# Throwing_POW_Supply.net
KiCad netlist of a schematic drawn in EAGLE
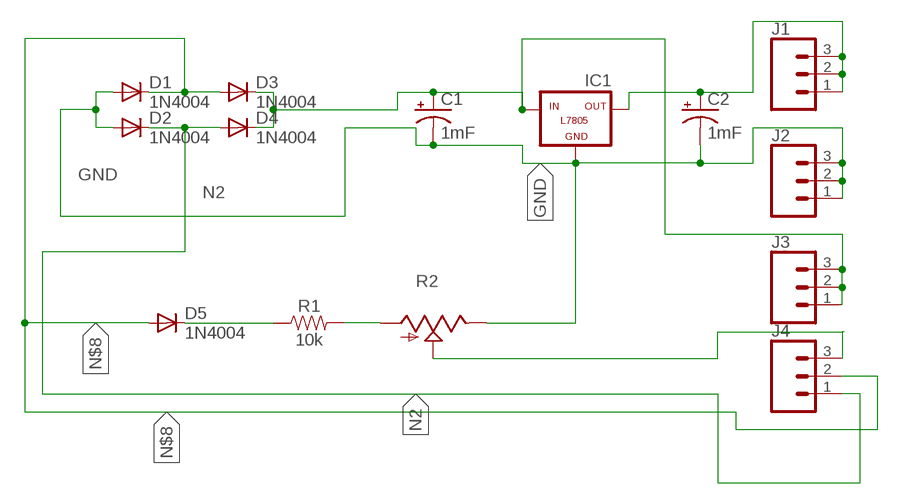
[diagram p0: schematic, sheet 1]

(export (version "E")
  (design (tool "Eeschema 10.0.6"))
  (components
    (comp (ref "C1")
      (value "1mF")
      (footprint "eagle-import:CPOL-RADIAL-5MM-10MM")
      (libsource (lib "eagle-import") (part "1000UF-RADIAL-5MM-25V-20%"))
    )
    (comp (ref "C2")
      (value "1mF")
      (footprint "eagle-import:CPOL-RADIAL-5MM-10MM")
      (libsource (lib "eagle-import") (part "1000UF-RADIAL-5MM-25V-20%"))
    )
    (comp (ref "D1")
      (value "1N4004")
      (footprint "eagle-import:DO41-10")
      (libsource (lib "eagle-import") (part "1N4004"))
    )
    (comp (ref "D2")
      (value "1N4004")
      (footprint "eagle-import:DO41-10")
      (libsource (lib "eagle-import") (part "1N4004"))
    )
    (comp (ref "D3")
      (value "1N4004")
      (footprint "eagle-import:DO41-10")
      (libsource (lib "eagle-import") (part "1N4004"))
    )
    (comp (ref "D4")
      (value "1N4004")
      (footprint "eagle-import:DO41-10")
      (libsource (lib "eagle-import") (part "1N4004"))
    )
    (comp (ref "D5")
      (value "1N4004")
      (footprint "eagle-import:DO41-10")
      (libsource (lib "eagle-import") (part "1N4004"))
    )
    (comp (ref "IC1")
      (value "L7805")
      (footprint "eagle-import:78XXL")
      (libsource (lib "eagle-import") (part "L7805"))
    )
    (comp (ref "J1")
      (value "CONN_03")
      (footprint "eagle-import:1X03")
      (libsource (lib "eagle-import") (part "CONN_03"))
    )
    (comp (ref "J2")
      (value "CONN_03")
      (footprint "eagle-import:1X03")
      (libsource (lib "eagle-import") (part "CONN_03"))
    )
    (comp (ref "J3")
      (value "CONN_03")
      (footprint "eagle-import:1X03")
      (libsource (lib "eagle-import") (part "CONN_03"))
    )
    (comp (ref "J4")
      (value "CONN_03")
      (footprint "eagle-import:1X03")
      (libsource (lib "eagle-import") (part "CONN_03"))
    )
    (comp (ref "R1")
      (value "10k")
      (footprint "eagle-import:AXIAL-0.3")
      (libsource (lib "eagle-import") (part "10KOHM-HORIZ-1/4W-1%"))
    )
    (comp (ref "R2")
      (value "TRIM_US-B25P")
      (footprint "eagle-import:B25P")
      (libsource (lib "eagle-import") (part "TRIM_US-B25P"))
    )
  )
  (nets
    (net (code "1") (name "GND") (class "Default")
      (node (ref "C1") (pin "-") (pinfunction "-_-") (pintype "passive"))
      (node (ref "C2") (pin "-") (pinfunction "-_-") (pintype "passive"))
      (node (ref "D1") (pin "A") (pinfunction "A_A") (pintype "passive"))
      (node (ref "D2") (pin "A") (pinfunction "A_A") (pintype "passive"))
      (node (ref "IC1") (pin "GND") (pinfunction "GND_GND") (pintype "input"))
      (node (ref "J2") (pin "1") (pinfunction "1_1") (pintype "passive"))
      (node (ref "J2") (pin "2") (pinfunction "2_2") (pintype "passive"))
      (node (ref "J2") (pin "3") (pinfunction "3_3") (pintype "passive"))
      (node (ref "R2") (pin "E") (pinfunction "E_E") (pintype "passive"))
    )
    (net (code "2") (name "N$8") (class "Default")
      (node (ref "D1") (pin "C") (pinfunction "C_C") (pintype "passive"))
      (node (ref "D3") (pin "A") (pinfunction "A_A") (pintype "passive"))
      (node (ref "D5") (pin "A") (pinfunction "A_A") (pintype "passive"))
      (node (ref "J4") (pin "2") (pinfunction "2_2") (pintype "passive"))
    )
    (net (code "3") (name "N2") (class "Default")
      (node (ref "D2") (pin "C") (pinfunction "C_C") (pintype "passive"))
      (node (ref "D4") (pin "A") (pinfunction "A_A") (pintype "passive"))
      (node (ref "J4") (pin "1") (pinfunction "1_1") (pintype "passive"))
    )
    (net (code "4") (name "Net-(C1-Pad+)") (class "Default")
      (node (ref "C1") (pin "+") (pinfunction "+_+") (pintype "passive"))
      (node (ref "D3") (pin "C") (pinfunction "C_C") (pintype "passive"))
      (node (ref "D4") (pin "C") (pinfunction "C_C") (pintype "passive"))
      (node (ref "IC1") (pin "IN") (pinfunction "IN_IN") (pintype "input"))
      (node (ref "J3") (pin "1") (pinfunction "1_1") (pintype "passive"))
      (node (ref "J3") (pin "2") (pinfunction "2_2") (pintype "passive"))
      (node (ref "J3") (pin "3") (pinfunction "3_3") (pintype "passive"))
    )
    (net (code "5") (name "Net-(C2-Pad+)") (class "Default")
      (node (ref "C2") (pin "+") (pinfunction "+_+") (pintype "passive"))
      (node (ref "IC1") (pin "OUT") (pinfunction "OUT_OUT") (pintype "passive"))
      (node (ref "J1") (pin "1") (pinfunction "1_1") (pintype "passive"))
      (node (ref "J1") (pin "2") (pinfunction "2_2") (pintype "passive"))
      (node (ref "J1") (pin "3") (pinfunction "3_3") (pintype "passive"))
    )
    (net (code "6") (name "Net-(J4-Pad3)") (class "Default")
      (node (ref "J4") (pin "3") (pinfunction "3_3") (pintype "passive"))
      (node (ref "R2") (pin "S") (pinfunction "S_S") (pintype "passive"))
    )
    (net (code "7") (name "Net-(R1-1)") (class "Default")
      (node (ref "D5") (pin "C") (pinfunction "C_C") (pintype "passive"))
      (node (ref "R1") (pin "P$1") (pinfunction "1_P$1") (pintype "passive"))
    )
    (net (code "8") (name "Net-(R1-2)") (class "Default")
      (node (ref "R1") (pin "P$2") (pinfunction "2_P$2") (pintype "passive"))
      (node (ref "R2") (pin "A") (pinfunction "A_A") (pintype "passive"))
    )
  )
)
